# ProPrj_FK407M3-VET6-V1_1-LCD-EB_2024-11-.net
KiCad netlist of a schematic drawn in EasyEDA Pro
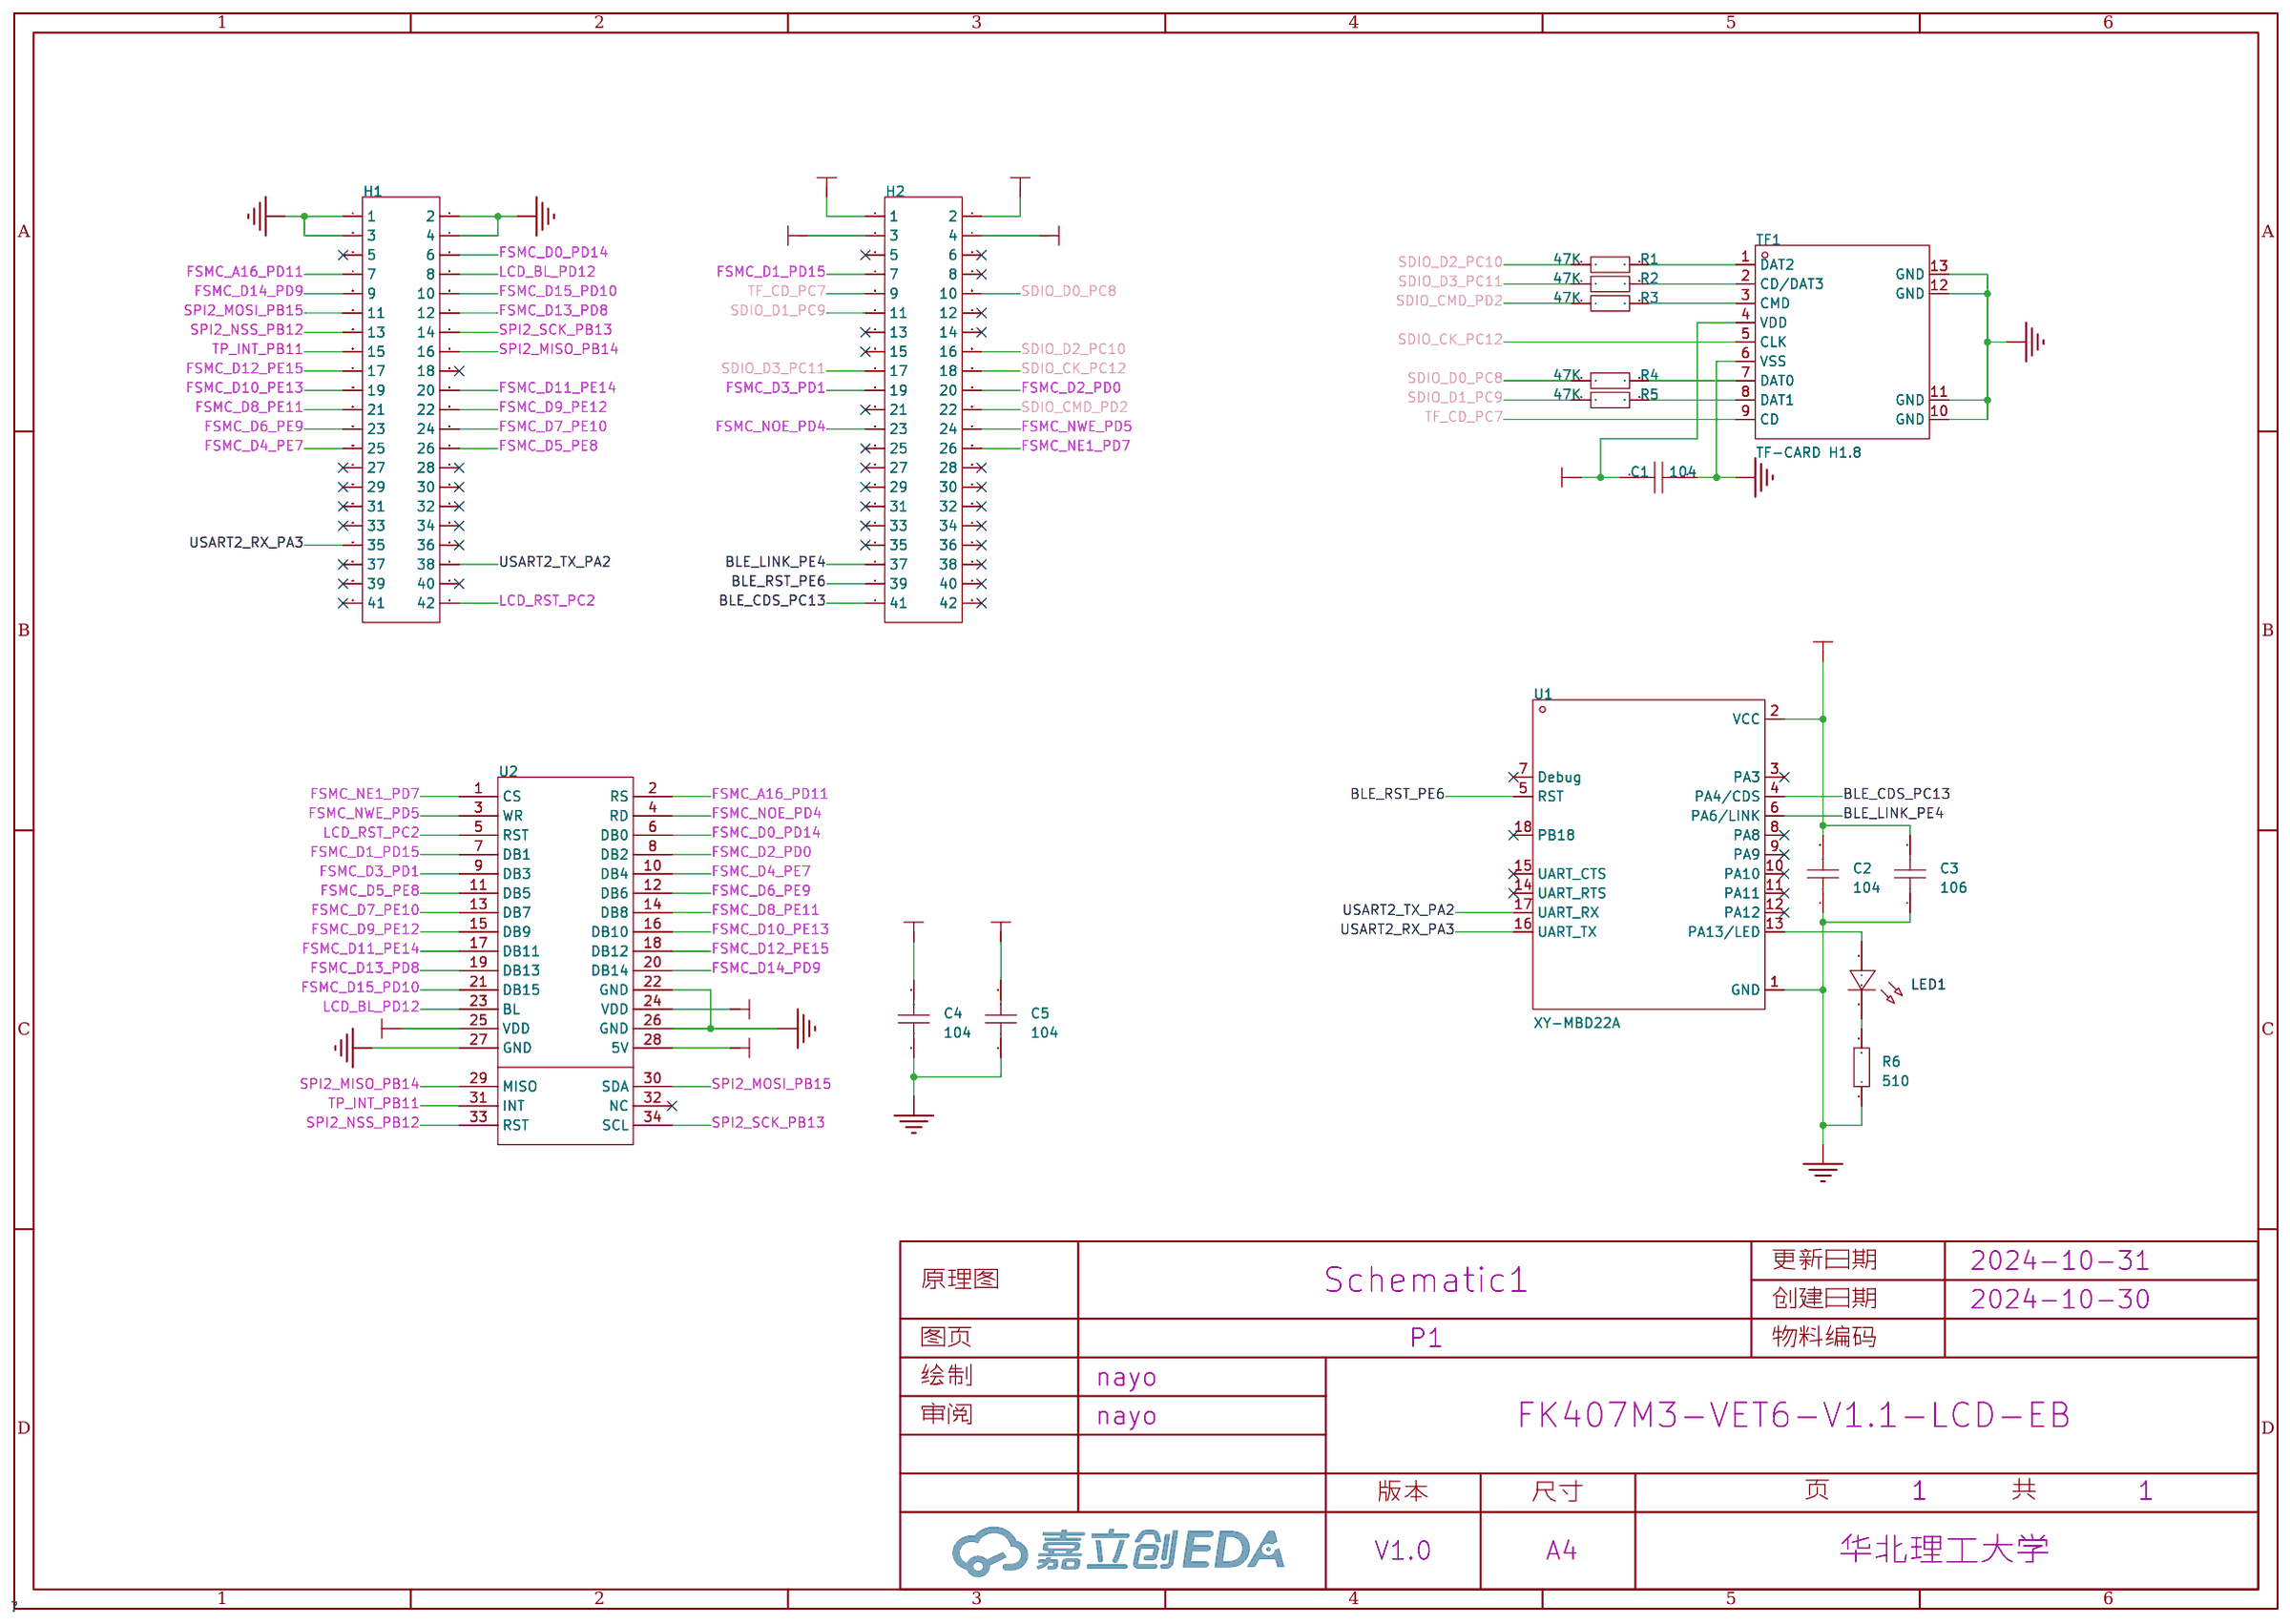
[diagram p0: schematic sheet]

(export (version "E")
  (design (tool "Eeschema 10.0.6"))
  (components
    (comp (ref "C1")
      (value "104")
      (footprint "easyedapro:C0603")
      (libsource (lib "easyedapro") (part "CapAcitance"))
    )
    (comp (ref "C2")
      (value "104")
      (footprint "easyedapro:C0603")
      (libsource (lib "easyedapro") (part "CapAcitance"))
    )
    (comp (ref "C3")
      (value "106")
      (footprint "easyedapro:C0603")
      (libsource (lib "easyedapro") (part "CapAcitance"))
    )
    (comp (ref "C4")
      (value "104")
      (footprint "easyedapro:C0603")
      (libsource (lib "easyedapro") (part "CapAcitance"))
    )
    (comp (ref "C5")
      (value "104")
      (footprint "easyedapro:C0603")
      (libsource (lib "easyedapro") (part "CapAcitance"))
    )
    (comp (ref "H1")
      (value "~")
      (footprint "easyedapro:HDR-F_2.54_2x21P")
      (libsource (lib "easyedapro") (part "HDR-F_2.54_2x21P"))
    )
    (comp (ref "H2")
      (value "~")
      (footprint "easyedapro:HDR-F_2.54_2x21P")
      (libsource (lib "easyedapro") (part "HDR-F_2.54_2x21P"))
    )
    (comp (ref "LED1")
      (value "~")
      (footprint "easyedapro:LED_0603")
      (libsource (lib "easyedapro") (part "LED_B"))
    )
    (comp (ref "R1") (value "47K") (footprint "easyedapro:R0603") (libsource (lib "easyedapro") (part "电阻")))
    (comp (ref "R2") (value "47K") (footprint "easyedapro:R0603") (libsource (lib "easyedapro") (part "电阻")))
    (comp (ref "R3") (value "47K") (footprint "easyedapro:R0603") (libsource (lib "easyedapro") (part "电阻")))
    (comp (ref "R4") (value "47K") (footprint "easyedapro:R0603") (libsource (lib "easyedapro") (part "电阻")))
    (comp (ref "R5") (value "47K") (footprint "easyedapro:R0603") (libsource (lib "easyedapro") (part "电阻")))
    (comp (ref "R6") (value "510") (footprint "easyedapro:R0603") (libsource (lib "easyedapro") (part "电阻")))
    (comp (ref "TF1")
      (value "TF-CARD H1.8")
      (footprint "easyedapro:TF-SMD_TF-CARD-H1.8")
      (description "卡连接方式:自弹式;卡类型:MicroSD卡(TF卡);连接器类型:卡座;本体最大高度:1.8mm;触头材质:铜合金;触头镀层:金;工作温度范围:-40°C~+70°C;")
      (fields (field (name "Manufacturer") "SHOU HAN(首韩)"))
      (libsource (lib "easyedapro") (part "TF-CARD H1.8"))
    )
    (comp (ref "U1")
      (value "XY-MBD22A")
      (footprint "easyedapro:wirelm-smd_xy-mbd22a")
      (libsource (lib "easyedapro") (part "XY-MBD22A"))
    )
    (comp (ref "U2")
      (value "~")
      (footprint "easyedapro:耀元鸿3.5寸TFT液晶显示屏并口串口电阻屏5点电容屏GT911彩屏LCD")
      (libsource (lib "easyedapro") (part "耀元鸿3.5寸TFT液晶显示屏并口串口电阻屏5点电容屏GT911彩屏LCD"))
    )
  )
  (nets
    (net (code "1") (name "/BLE_CDS_PC13") (class "Default")
      (node (ref "H2") (pin "41") (pinfunction "41_41") (pintype "input"))
      (node (ref "U1") (pin "4") (pinfunction "PA4/CDS_4") (pintype "unspecified"))
    )
    (net (code "2") (name "/BLE_LINK_PE4") (class "Default")
      (node (ref "H2") (pin "37") (pinfunction "37_37") (pintype "input"))
      (node (ref "U1") (pin "6") (pinfunction "PA6/LINK_6") (pintype "unspecified"))
    )
    (net (code "3") (name "/BLE_RST_PE6") (class "Default")
      (node (ref "H2") (pin "39") (pinfunction "39_39") (pintype "input"))
      (node (ref "U1") (pin "5") (pinfunction "RST_5") (pintype "unspecified"))
    )
    (net (code "4") (name "/FSMC_A16_PD11") (class "Default")
      (node (ref "H1") (pin "7") (pinfunction "7_7") (pintype "input"))
      (node (ref "U2") (pin "2") (pinfunction "RS_2") (pintype "input"))
    )
    (net (code "5") (name "/FSMC_D0_PD14") (class "Default")
      (node (ref "H1") (pin "6") (pinfunction "6_6") (pintype "input"))
      (node (ref "U2") (pin "6") (pinfunction "DB0_6") (pintype "input"))
    )
    (net (code "6") (name "/FSMC_D1_PD15") (class "Default")
      (node (ref "H2") (pin "7") (pinfunction "7_7") (pintype "input"))
      (node (ref "U2") (pin "7") (pinfunction "DB1_7") (pintype "input"))
    )
    (net (code "7") (name "/FSMC_D2_PD0") (class "Default")
      (node (ref "H2") (pin "20") (pinfunction "20_20") (pintype "input"))
      (node (ref "U2") (pin "8") (pinfunction "DB2_8") (pintype "input"))
    )
    (net (code "8") (name "/FSMC_D3_PD1") (class "Default")
      (node (ref "H2") (pin "19") (pinfunction "19_19") (pintype "input"))
      (node (ref "U2") (pin "9") (pinfunction "DB3_9") (pintype "input"))
    )
    (net (code "9") (name "/FSMC_D4_PE7") (class "Default")
      (node (ref "H1") (pin "25") (pinfunction "25_25") (pintype "input"))
      (node (ref "U2") (pin "10") (pinfunction "DB4_10") (pintype "input"))
    )
    (net (code "10") (name "/FSMC_D5_PE8") (class "Default")
      (node (ref "H1") (pin "26") (pinfunction "26_26") (pintype "input"))
      (node (ref "U2") (pin "11") (pinfunction "DB5_11") (pintype "input"))
    )
    (net (code "11") (name "/FSMC_D6_PE9") (class "Default")
      (node (ref "H1") (pin "23") (pinfunction "23_23") (pintype "input"))
      (node (ref "U2") (pin "12") (pinfunction "DB6_12") (pintype "input"))
    )
    (net (code "12") (name "/FSMC_D7_PE10") (class "Default")
      (node (ref "H1") (pin "24") (pinfunction "24_24") (pintype "input"))
      (node (ref "U2") (pin "13") (pinfunction "DB7_13") (pintype "input"))
    )
    (net (code "13") (name "/FSMC_D8_PE11") (class "Default")
      (node (ref "H1") (pin "21") (pinfunction "21_21") (pintype "input"))
      (node (ref "U2") (pin "14") (pinfunction "DB8_14") (pintype "input"))
    )
    (net (code "14") (name "/FSMC_D9_PE12") (class "Default")
      (node (ref "H1") (pin "22") (pinfunction "22_22") (pintype "input"))
      (node (ref "U2") (pin "15") (pinfunction "DB9_15") (pintype "input"))
    )
    (net (code "15") (name "/FSMC_D10_PE13") (class "Default")
      (node (ref "H1") (pin "19") (pinfunction "19_19") (pintype "input"))
      (node (ref "U2") (pin "16") (pinfunction "DB10_16") (pintype "input"))
    )
    (net (code "16") (name "/FSMC_D11_PE14") (class "Default")
      (node (ref "H1") (pin "20") (pinfunction "20_20") (pintype "input"))
      (node (ref "U2") (pin "17") (pinfunction "DB11_17") (pintype "input"))
    )
    (net (code "17") (name "/FSMC_D12_PE15") (class "Default")
      (node (ref "H1") (pin "17") (pinfunction "17_17") (pintype "input"))
      (node (ref "U2") (pin "18") (pinfunction "DB12_18") (pintype "input"))
    )
    (net (code "18") (name "/FSMC_D13_PD8") (class "Default")
      (node (ref "H1") (pin "12") (pinfunction "12_12") (pintype "input"))
      (node (ref "U2") (pin "19") (pinfunction "DB13_19") (pintype "input"))
    )
    (net (code "19") (name "/FSMC_D14_PD9") (class "Default")
      (node (ref "H1") (pin "9") (pinfunction "9_9") (pintype "input"))
      (node (ref "U2") (pin "20") (pinfunction "DB14_20") (pintype "input"))
    )
    (net (code "20") (name "/FSMC_D15_PD10") (class "Default")
      (node (ref "H1") (pin "10") (pinfunction "10_10") (pintype "input"))
      (node (ref "U2") (pin "21") (pinfunction "DB15_21") (pintype "input"))
    )
    (net (code "21") (name "/FSMC_NE1_PD7") (class "Default")
      (node (ref "H2") (pin "26") (pinfunction "26_26") (pintype "input"))
      (node (ref "U2") (pin "1") (pinfunction "CS_1") (pintype "input"))
    )
    (net (code "22") (name "/FSMC_NOE_PD4") (class "Default")
      (node (ref "H2") (pin "23") (pinfunction "23_23") (pintype "input"))
      (node (ref "U2") (pin "4") (pinfunction "RD_4") (pintype "input"))
    )
    (net (code "23") (name "/FSMC_NWE_PD5") (class "Default")
      (node (ref "H2") (pin "24") (pinfunction "24_24") (pintype "input"))
      (node (ref "U2") (pin "3") (pinfunction "WR_3") (pintype "input"))
    )
    (net (code "24") (name "/LCD_BL_PD12") (class "Default")
      (node (ref "H1") (pin "8") (pinfunction "8_8") (pintype "input"))
      (node (ref "U2") (pin "23") (pinfunction "BL_23") (pintype "input"))
    )
    (net (code "25") (name "/LCD_RST_PC2") (class "Default")
      (node (ref "H1") (pin "42") (pinfunction "42_42") (pintype "input"))
      (node (ref "U2") (pin "5") (pinfunction "RST_5") (pintype "input"))
    )
    (net (code "26") (name "/SDIO_CK_PC12") (class "Default")
      (node (ref "H2") (pin "18") (pinfunction "18_18") (pintype "input"))
      (node (ref "TF1") (pin "5") (pinfunction "CLK_5") (pintype "unspecified"))
    )
    (net (code "27") (name "/SDIO_CMD_PD2") (class "Default")
      (node (ref "H2") (pin "22") (pinfunction "22_22") (pintype "input"))
      (node (ref "R3") (pin "1") (pinfunction "1_1") (pintype "input"))
    )
    (net (code "28") (name "/SDIO_D0_PC8") (class "Default")
      (node (ref "H2") (pin "10") (pinfunction "10_10") (pintype "input"))
      (node (ref "R4") (pin "1") (pinfunction "1_1") (pintype "input"))
    )
    (net (code "29") (name "/SDIO_D1_PC9") (class "Default")
      (node (ref "H2") (pin "11") (pinfunction "11_11") (pintype "input"))
      (node (ref "R5") (pin "1") (pinfunction "1_1") (pintype "input"))
    )
    (net (code "30") (name "/SDIO_D2_PC10") (class "Default")
      (node (ref "H2") (pin "16") (pinfunction "16_16") (pintype "input"))
      (node (ref "R1") (pin "1") (pinfunction "1_1") (pintype "input"))
    )
    (net (code "31") (name "/SDIO_D3_PC11") (class "Default")
      (node (ref "H2") (pin "17") (pinfunction "17_17") (pintype "input"))
      (node (ref "R2") (pin "1") (pinfunction "1_1") (pintype "input"))
    )
    (net (code "32") (name "/SPI2_MISO_PB14") (class "Default")
      (node (ref "H1") (pin "16") (pinfunction "16_16") (pintype "input"))
      (node (ref "U2") (pin "29") (pinfunction "MISO_29") (pintype "input"))
    )
    (net (code "33") (name "/SPI2_MOSI_PB15") (class "Default")
      (node (ref "H1") (pin "11") (pinfunction "11_11") (pintype "input"))
      (node (ref "U2") (pin "30") (pinfunction "SDA_30") (pintype "input"))
    )
    (net (code "34") (name "/SPI2_NSS_PB12") (class "Default")
      (node (ref "H1") (pin "13") (pinfunction "13_13") (pintype "input"))
      (node (ref "U2") (pin "33") (pinfunction "RST_33") (pintype "input"))
    )
    (net (code "35") (name "/SPI2_SCK_PB13") (class "Default")
      (node (ref "H1") (pin "14") (pinfunction "14_14") (pintype "input"))
      (node (ref "U2") (pin "34") (pinfunction "SCL_34") (pintype "input"))
    )
    (net (code "36") (name "/TF_CD_PC7") (class "Default")
      (node (ref "H2") (pin "9") (pinfunction "9_9") (pintype "input"))
      (node (ref "TF1") (pin "9") (pinfunction "CD_9") (pintype "unspecified"))
    )
    (net (code "37") (name "/TP_INT_PB11") (class "Default")
      (node (ref "H1") (pin "15") (pinfunction "15_15") (pintype "input"))
      (node (ref "U2") (pin "31") (pinfunction "INT_31") (pintype "input"))
    )
    (net (code "38") (name "/USART2_RX_PA3") (class "Default")
      (node (ref "H1") (pin "35") (pinfunction "35_35") (pintype "input"))
      (node (ref "U1") (pin "16") (pinfunction "UART_TX_16") (pintype "unspecified"))
    )
    (net (code "39") (name "/USART2_TX_PA2") (class "Default")
      (node (ref "H1") (pin "38") (pinfunction "38_38") (pintype "input"))
      (node (ref "U1") (pin "17") (pinfunction "UART_RX_17") (pintype "unspecified"))
    )
    (net (code "40") (name "3V3") (class "Default")
      (node (ref "C1") (pin "1") (pinfunction "1_1") (pintype "input"))
      (node (ref "C2") (pin "2") (pinfunction "2_2") (pintype "input"))
      (node (ref "C3") (pin "2") (pinfunction "2_2") (pintype "input"))
      (node (ref "C5") (pin "2") (pinfunction "2_2") (pintype "input"))
      (node (ref "H2") (pin "3") (pinfunction "3_3") (pintype "input"))
      (node (ref "H2") (pin "4") (pinfunction "4_4") (pintype "input"))
      (node (ref "TF1") (pin "4") (pinfunction "VDD_4") (pintype "unspecified"))
      (node (ref "U1") (pin "2") (pinfunction "VCC_2") (pintype "unspecified"))
      (node (ref "U2") (pin "24") (pinfunction "VDD_24") (pintype "input"))
      (node (ref "U2") (pin "25") (pinfunction "VDD_25") (pintype "input"))
    )
    (net (code "41") (name "5V") (class "Default")
      (node (ref "C4") (pin "2") (pinfunction "2_2") (pintype "input"))
      (node (ref "H2") (pin "1") (pinfunction "1_1") (pintype "input"))
      (node (ref "H2") (pin "2") (pinfunction "2_2") (pintype "input"))
      (node (ref "U2") (pin "28") (pinfunction "5V_28") (pintype "input"))
    )
    (net (code "42") (name "GND") (class "Default")
      (node (ref "C1") (pin "2") (pinfunction "2_2") (pintype "input"))
      (node (ref "C2") (pin "1") (pinfunction "1_1") (pintype "input"))
      (node (ref "C3") (pin "1") (pinfunction "1_1") (pintype "input"))
      (node (ref "C4") (pin "1") (pinfunction "1_1") (pintype "input"))
      (node (ref "C5") (pin "1") (pinfunction "1_1") (pintype "input"))
      (node (ref "H1") (pin "1") (pinfunction "1_1") (pintype "input"))
      (node (ref "H1") (pin "2") (pinfunction "2_2") (pintype "input"))
      (node (ref "H1") (pin "3") (pinfunction "3_3") (pintype "input"))
      (node (ref "H1") (pin "4") (pinfunction "4_4") (pintype "input"))
      (node (ref "R6") (pin "1") (pinfunction "1_1") (pintype "input"))
      (node (ref "TF1") (pin "10") (pinfunction "GND_10") (pintype "unspecified"))
      (node (ref "TF1") (pin "11") (pinfunction "GND_11") (pintype "unspecified"))
      (node (ref "TF1") (pin "12") (pinfunction "GND_12") (pintype "unspecified"))
      (node (ref "TF1") (pin "13") (pinfunction "GND_13") (pintype "unspecified"))
      (node (ref "TF1") (pin "6") (pinfunction "VSS_6") (pintype "unspecified"))
      (node (ref "U1") (pin "1") (pinfunction "GND_1") (pintype "unspecified"))
      (node (ref "U2") (pin "22") (pinfunction "GND_22") (pintype "input"))
      (node (ref "U2") (pin "26") (pinfunction "GND_26") (pintype "input"))
      (node (ref "U2") (pin "27") (pinfunction "GND_27") (pintype "input"))
    )
    (net (code "43") (name "Net-(LED1-A)") (class "Default")
      (node (ref "LED1") (pin "2") (pinfunction "A_2") (pintype "input"))
      (node (ref "U1") (pin "13") (pinfunction "PA13/LED_13") (pintype "unspecified"))
    )
    (net (code "44") (name "Net-(LED1-C)") (class "Default")
      (node (ref "LED1") (pin "1") (pinfunction "C_1") (pintype "input"))
      (node (ref "R6") (pin "2") (pinfunction "2_2") (pintype "input"))
    )
    (net (code "45") (name "Net-(TF1-CD{slash}DAT3)") (class "Default")
      (node (ref "R2") (pin "2") (pinfunction "2_2") (pintype "input"))
      (node (ref "TF1") (pin "2") (pinfunction "CD/DAT3_2") (pintype "unspecified"))
    )
    (net (code "46") (name "Net-(TF1-CMD)") (class "Default")
      (node (ref "R3") (pin "2") (pinfunction "2_2") (pintype "input"))
      (node (ref "TF1") (pin "3") (pinfunction "CMD_3") (pintype "unspecified"))
    )
    (net (code "47") (name "Net-(TF1-DAT0)") (class "Default")
      (node (ref "R4") (pin "2") (pinfunction "2_2") (pintype "input"))
      (node (ref "TF1") (pin "7") (pinfunction "DAT0_7") (pintype "unspecified"))
    )
    (net (code "48") (name "Net-(TF1-DAT1)") (class "Default")
      (node (ref "R5") (pin "2") (pinfunction "2_2") (pintype "input"))
      (node (ref "TF1") (pin "8") (pinfunction "DAT1_8") (pintype "unspecified"))
    )
    (net (code "49") (name "Net-(TF1-DAT2)") (class "Default")
      (node (ref "R1") (pin "2") (pinfunction "2_2") (pintype "input"))
      (node (ref "TF1") (pin "1") (pinfunction "DAT2_1") (pintype "unspecified"))
    )
    (net (code "50") (name "unconnected-(H1-Pad5)") (class "Default")
      (node (ref "H1") (pin "5") (pinfunction "5_5") (pintype "input+no_connect"))
    )
    (net (code "51") (name "unconnected-(H1-Pad18)") (class "Default")
      (node (ref "H1") (pin "18") (pinfunction "18_18") (pintype "input+no_connect"))
    )
    (net (code "52") (name "unconnected-(H1-Pad27)") (class "Default")
      (node (ref "H1") (pin "27") (pinfunction "27_27") (pintype "input+no_connect"))
    )
    (net (code "53") (name "unconnected-(H1-Pad28)") (class "Default")
      (node (ref "H1") (pin "28") (pinfunction "28_28") (pintype "input+no_connect"))
    )
    (net (code "54") (name "unconnected-(H1-Pad29)") (class "Default")
      (node (ref "H1") (pin "29") (pinfunction "29_29") (pintype "input+no_connect"))
    )
    (net (code "55") (name "unconnected-(H1-Pad30)") (class "Default")
      (node (ref "H1") (pin "30") (pinfunction "30_30") (pintype "input+no_connect"))
    )
    (net (code "56") (name "unconnected-(H1-Pad31)") (class "Default")
      (node (ref "H1") (pin "31") (pinfunction "31_31") (pintype "input+no_connect"))
    )
    (net (code "57") (name "unconnected-(H1-Pad32)") (class "Default")
      (node (ref "H1") (pin "32") (pinfunction "32_32") (pintype "input+no_connect"))
    )
    (net (code "58") (name "unconnected-(H1-Pad33)") (class "Default")
      (node (ref "H1") (pin "33") (pinfunction "33_33") (pintype "input+no_connect"))
    )
    (net (code "59") (name "unconnected-(H1-Pad34)") (class "Default")
      (node (ref "H1") (pin "34") (pinfunction "34_34") (pintype "input+no_connect"))
    )
    (net (code "60") (name "unconnected-(H1-Pad36)") (class "Default")
      (node (ref "H1") (pin "36") (pinfunction "36_36") (pintype "input+no_connect"))
    )
    (net (code "61") (name "unconnected-(H1-Pad37)") (class "Default")
      (node (ref "H1") (pin "37") (pinfunction "37_37") (pintype "input+no_connect"))
    )
    (net (code "62") (name "unconnected-(H1-Pad39)") (class "Default")
      (node (ref "H1") (pin "39") (pinfunction "39_39") (pintype "input+no_connect"))
    )
    (net (code "63") (name "unconnected-(H1-Pad40)") (class "Default")
      (node (ref "H1") (pin "40") (pinfunction "40_40") (pintype "input+no_connect"))
    )
    (net (code "64") (name "unconnected-(H1-Pad41)") (class "Default")
      (node (ref "H1") (pin "41") (pinfunction "41_41") (pintype "input+no_connect"))
    )
    (net (code "65") (name "unconnected-(H2-Pad5)") (class "Default")
      (node (ref "H2") (pin "5") (pinfunction "5_5") (pintype "input+no_connect"))
    )
    (net (code "66") (name "unconnected-(H2-Pad6)") (class "Default")
      (node (ref "H2") (pin "6") (pinfunction "6_6") (pintype "input+no_connect"))
    )
    (net (code "67") (name "unconnected-(H2-Pad8)") (class "Default")
      (node (ref "H2") (pin "8") (pinfunction "8_8") (pintype "input+no_connect"))
    )
    (net (code "68") (name "unconnected-(H2-Pad12)") (class "Default")
      (node (ref "H2") (pin "12") (pinfunction "12_12") (pintype "input+no_connect"))
    )
    (net (code "69") (name "unconnected-(H2-Pad13)") (class "Default")
      (node (ref "H2") (pin "13") (pinfunction "13_13") (pintype "input+no_connect"))
    )
    (net (code "70") (name "unconnected-(H2-Pad14)") (class "Default")
      (node (ref "H2") (pin "14") (pinfunction "14_14") (pintype "input+no_connect"))
    )
    (net (code "71") (name "unconnected-(H2-Pad15)") (class "Default")
      (node (ref "H2") (pin "15") (pinfunction "15_15") (pintype "input+no_connect"))
    )
    (net (code "72") (name "unconnected-(H2-Pad21)") (class "Default")
      (node (ref "H2") (pin "21") (pinfunction "21_21") (pintype "input+no_connect"))
    )
    (net (code "73") (name "unconnected-(H2-Pad25)") (class "Default")
      (node (ref "H2") (pin "25") (pinfunction "25_25") (pintype "input+no_connect"))
    )
    (net (code "74") (name "unconnected-(H2-Pad27)") (class "Default")
      (node (ref "H2") (pin "27") (pinfunction "27_27") (pintype "input+no_connect"))
    )
    (net (code "75") (name "unconnected-(H2-Pad28)") (class "Default")
      (node (ref "H2") (pin "28") (pinfunction "28_28") (pintype "input+no_connect"))
    )
    (net (code "76") (name "unconnected-(H2-Pad29)") (class "Default")
      (node (ref "H2") (pin "29") (pinfunction "29_29") (pintype "input+no_connect"))
    )
    (net (code "77") (name "unconnected-(H2-Pad30)") (class "Default")
      (node (ref "H2") (pin "30") (pinfunction "30_30") (pintype "input+no_connect"))
    )
    (net (code "78") (name "unconnected-(H2-Pad31)") (class "Default")
      (node (ref "H2") (pin "31") (pinfunction "31_31") (pintype "input+no_connect"))
    )
    (net (code "79") (name "unconnected-(H2-Pad32)") (class "Default")
      (node (ref "H2") (pin "32") (pinfunction "32_32") (pintype "input+no_connect"))
    )
    (net (code "80") (name "unconnected-(H2-Pad33)") (class "Default")
      (node (ref "H2") (pin "33") (pinfunction "33_33") (pintype "input+no_connect"))
    )
    (net (code "81") (name "unconnected-(H2-Pad34)") (class "Default")
      (node (ref "H2") (pin "34") (pinfunction "34_34") (pintype "input+no_connect"))
    )
    (net (code "82") (name "unconnected-(H2-Pad35)") (class "Default")
      (node (ref "H2") (pin "35") (pinfunction "35_35") (pintype "input+no_connect"))
    )
    (net (code "83") (name "unconnected-(H2-Pad36)") (class "Default")
      (node (ref "H2") (pin "36") (pinfunction "36_36") (pintype "input+no_connect"))
    )
    (net (code "84") (name "unconnected-(H2-Pad38)") (class "Default")
      (node (ref "H2") (pin "38") (pinfunction "38_38") (pintype "input+no_connect"))
    )
    (net (code "85") (name "unconnected-(H2-Pad40)") (class "Default")
      (node (ref "H2") (pin "40") (pinfunction "40_40") (pintype "input+no_connect"))
    )
    (net (code "86") (name "unconnected-(H2-Pad42)") (class "Default")
      (node (ref "H2") (pin "42") (pinfunction "42_42") (pintype "input+no_connect"))
    )
    (net (code "87") (name "unconnected-(U1-Debug-Pad7)") (class "Default")
      (node (ref "U1") (pin "7") (pinfunction "Debug_7") (pintype "unspecified+no_connect"))
    )
    (net (code "88") (name "unconnected-(U1-PA3-Pad3)") (class "Default")
      (node (ref "U1") (pin "3") (pinfunction "PA3_3") (pintype "unspecified+no_connect"))
    )
    (net (code "89") (name "unconnected-(U1-PA8-Pad8)") (class "Default")
      (node (ref "U1") (pin "8") (pinfunction "PA8_8") (pintype "unspecified+no_connect"))
    )
    (net (code "90") (name "unconnected-(U1-PA9-Pad9)") (class "Default")
      (node (ref "U1") (pin "9") (pinfunction "PA9_9") (pintype "unspecified+no_connect"))
    )
    (net (code "91") (name "unconnected-(U1-PA10-Pad10)") (class "Default")
      (node (ref "U1") (pin "10") (pinfunction "PA10_10") (pintype "unspecified+no_connect"))
    )
    (net (code "92") (name "unconnected-(U1-PA11-Pad11)") (class "Default")
      (node (ref "U1") (pin "11") (pinfunction "PA11_11") (pintype "unspecified+no_connect"))
    )
    (net (code "93") (name "unconnected-(U1-PA12-Pad12)") (class "Default")
      (node (ref "U1") (pin "12") (pinfunction "PA12_12") (pintype "unspecified+no_connect"))
    )
    (net (code "94") (name "unconnected-(U1-PB18-Pad18)") (class "Default")
      (node (ref "U1") (pin "18") (pinfunction "PB18_18") (pintype "unspecified+no_connect"))
    )
    (net (code "95") (name "unconnected-(U1-UART_CTS-Pad15)") (class "Default")
      (node (ref "U1") (pin "15") (pinfunction "UART_CTS_15") (pintype "unspecified+no_connect"))
    )
    (net (code "96") (name "unconnected-(U1-UART_RTS-Pad14)") (class "Default")
      (node (ref "U1") (pin "14") (pinfunction "UART_RTS_14") (pintype "unspecified+no_connect"))
    )
    (net (code "97") (name "unconnected-(U2-NC-Pad32)") (class "Default")
      (node (ref "U2") (pin "32") (pinfunction "NC_32") (pintype "input+no_connect"))
    )
  )
)
